# SSD1306.net
KiCad netlist of a schematic drawn in Altium Designer
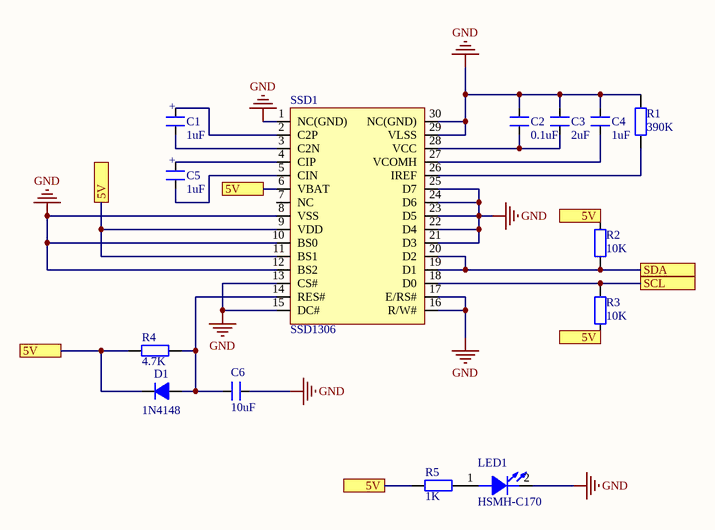
[diagram p0: SSD1306.SchDoc]

(export (version "E")
  (design (tool "Eeschema 10.0.6"))
  (components
    (comp (ref "C1")
      (value "1uF")
      (footprint "SM-0805")
      (description "Cap SMD")
      (libsource (lib "hphonglib") (part "CM"))
    )
    (comp (ref "C2")
      (value "0.1uF")
      (footprint "SM-0805")
      (description "Cap SMD")
      (libsource (lib "hphonglib") (part "CM"))
    )
    (comp (ref "C3")
      (value "2uF")
      (footprint "SM-0805")
      (description "Cap SMD")
      (libsource (lib "hphonglib") (part "CM"))
    )
    (comp (ref "C4")
      (value "1uF")
      (footprint "SM-0805")
      (description "Cap SMD")
      (libsource (lib "hphonglib") (part "CM"))
    )
    (comp (ref "C5")
      (value "1uF")
      (footprint "SM-0805")
      (description "Cap SMD")
      (libsource (lib "hphonglib") (part "CM"))
    )
    (comp (ref "C6")
      (value "10uF")
      (footprint "SM-0805")
      (description "Cap SMD")
      (libsource (lib "hphonglib") (part "CM"))
    )
    (comp (ref "D1")
      (value "Diode")
      (footprint "DO-214AC,SMA")
      (fields (field (name "PUBLISHER") "Altium Limited"))
      (libsource (lib "hphonglib") (part "Diode"))
    )
    (comp (ref "LED1")
      (value "HSMH-C170")
      (footprint "LED.SMD.GREEN")
      (description "Typical GaAs SMD LED")
      (fields (field (name "MANUFACTURER") "Lite-On Inc") (field (name "PUBLISHER") "Hoang Nguyen"))
      (libsource (lib "hphonglib") (part "LED_1"))
    )
    (comp (ref "R1")
      (value "390K")
      (footprint "DIEN TRO 0805")
      (description "RES_0805")
      (fields (field (name "Comment") "RES_SMD_0805") (field (name "PUBLISHER") "Altium Limited"))
      (libsource (lib "") (part "RES_SMD_0805_1"))
    )
    (comp (ref "R2")
      (value "10K")
      (footprint "DIEN TRO 0805")
      (description "RES_0805")
      (fields (field (name "Comment") "RES_SMD_0805") (field (name "PUBLISHER") "Altium Limited"))
      (libsource (lib "") (part "RES_SMD_0805_1"))
    )
    (comp (ref "R3")
      (value "10K")
      (footprint "DIEN TRO 0805")
      (description "RES_0805")
      (fields (field (name "Comment") "RES_SMD_0805") (field (name "PUBLISHER") "Altium Limited"))
      (libsource (lib "") (part "RES_SMD_0805_1"))
    )
    (comp (ref "R4")
      (value "4.7K")
      (footprint "DIEN TRO 0805")
      (description "RES_0805")
      (fields (field (name "Comment") "RES_SMD_0805") (field (name "PUBLISHER") "Altium Limited"))
      (libsource (lib "hphonglib") (part "RES_SMD_0805"))
    )
    (comp (ref "R5")
      (value "1K")
      (footprint "DIEN TRO 0805")
      (description "RES_0805")
      (fields (field (name "Comment") "RES_SMD_0805") (field (name "PUBLISHER") "Altium Limited"))
      (libsource (lib "hphonglib") (part "RES_SMD_0805"))
    )
    (comp (ref "SSD1")
      (value "SSD1306")
      (footprint "SSD1306")
      (libsource (lib "EMG_IoT_V2.0") (part "SSD1306"))
    )
  )
  (nets
    (net (code "1") (name "/5V") (class "Default")
      (node (ref "D1") (pin "2") (pinfunction "K_2") (pintype "passive"))
      (node (ref "R2") (pin "2") (pinfunction "2_2") (pintype "passive"))
      (node (ref "R3") (pin "1") (pinfunction "1_1") (pintype "passive"))
      (node (ref "R4") (pin "1") (pinfunction "1_1") (pintype "passive"))
      (node (ref "R5") (pin "1") (pinfunction "1_1") (pintype "passive"))
      (node (ref "SSD1") (pin "11") (pinfunction "BS1_11") (pintype "passive"))
      (node (ref "SSD1") (pin "6") (pinfunction "VBAT_6") (pintype "passive"))
      (node (ref "SSD1") (pin "9") (pinfunction "VDD_9") (pintype "passive"))
    )
    (net (code "2") (name "/SCL") (class "Default")
      (node (ref "R3") (pin "2") (pinfunction "2_2") (pintype "passive"))
      (node (ref "SSD1") (pin "18") (pinfunction "D0_18") (pintype "passive"))
    )
    (net (code "3") (name "/SDA") (class "Default")
      (node (ref "R2") (pin "1") (pinfunction "1_1") (pintype "passive"))
      (node (ref "SSD1") (pin "19") (pinfunction "D1_19") (pintype "passive"))
      (node (ref "SSD1") (pin "20") (pinfunction "D2_20") (pintype "passive"))
    )
    (net (code "4") (name "GND") (class "Default")
      (node (ref "C2") (pin "2") (pinfunction "2_2") (pintype "passive"))
      (node (ref "C3") (pin "2") (pinfunction "2_2") (pintype "passive"))
      (node (ref "C4") (pin "2") (pinfunction "2_2") (pintype "passive"))
      (node (ref "C6") (pin "2") (pinfunction "2_2") (pintype "passive"))
      (node (ref "LED1") (pin "2") (pinfunction "K_2") (pintype "passive"))
      (node (ref "R1") (pin "2") (pinfunction "2_2") (pintype "passive"))
      (node (ref "SSD1") (pin "1") (pinfunction "NC(GND)_1") (pintype "passive"))
      (node (ref "SSD1") (pin "10") (pinfunction "BS0_10") (pintype "passive"))
      (node (ref "SSD1") (pin "12") (pinfunction "BS2_12") (pintype "passive"))
      (node (ref "SSD1") (pin "13") (pinfunction "CS#_13") (pintype "passive"))
      (node (ref "SSD1") (pin "15") (pinfunction "DC#_15") (pintype "passive"))
      (node (ref "SSD1") (pin "16") (pinfunction "R/W#_16") (pintype "passive"))
      (node (ref "SSD1") (pin "17") (pinfunction "E/RS#_17") (pintype "passive"))
      (node (ref "SSD1") (pin "21") (pinfunction "D3_21") (pintype "passive"))
      (node (ref "SSD1") (pin "22") (pinfunction "D4_22") (pintype "passive"))
      (node (ref "SSD1") (pin "23") (pinfunction "D5_23") (pintype "passive"))
      (node (ref "SSD1") (pin "24") (pinfunction "D6_24") (pintype "passive"))
      (node (ref "SSD1") (pin "25") (pinfunction "D7_25") (pintype "passive"))
      (node (ref "SSD1") (pin "29") (pinfunction "VLSS_29") (pintype "passive"))
      (node (ref "SSD1") (pin "30") (pinfunction "NC(GND)_30") (pintype "passive"))
      (node (ref "SSD1") (pin "8") (pinfunction "VSS_8") (pintype "passive"))
    )
    (net (code "5") (name "Net-(D1-A)") (class "Default")
      (node (ref "C6") (pin "1") (pinfunction "1_1") (pintype "passive"))
      (node (ref "D1") (pin "1") (pinfunction "A_1") (pintype "passive"))
      (node (ref "R4") (pin "2") (pinfunction "2_2") (pintype "passive"))
      (node (ref "SSD1") (pin "14") (pinfunction "RES#_14") (pintype "passive"))
    )
    (net (code "6") (name "Net-(LED1-A)") (class "Default")
      (node (ref "LED1") (pin "1") (pinfunction "A_1") (pintype "passive"))
      (node (ref "R5") (pin "2") (pinfunction "2_2") (pintype "passive"))
    )
    (net (code "7") (name "Net-(SSD1-C2N)") (class "Default")
      (node (ref "C1") (pin "1") (pinfunction "1_1") (pintype "passive"))
      (node (ref "SSD1") (pin "3") (pinfunction "C2N_3") (pintype "passive"))
    )
    (net (code "8") (name "Net-(SSD1-C2P)") (class "Default")
      (node (ref "C1") (pin "2") (pinfunction "2_2") (pintype "passive"))
      (node (ref "SSD1") (pin "2") (pinfunction "C2P_2") (pintype "passive"))
    )
    (net (code "9") (name "Net-(SSD1-CIN)") (class "Default")
      (node (ref "C5") (pin "1") (pinfunction "1_1") (pintype "passive"))
      (node (ref "SSD1") (pin "5") (pinfunction "CIN_5") (pintype "passive"))
    )
    (net (code "10") (name "Net-(SSD1-CIP)") (class "Default")
      (node (ref "C5") (pin "2") (pinfunction "2_2") (pintype "passive"))
      (node (ref "SSD1") (pin "4") (pinfunction "CIP_4") (pintype "passive"))
    )
    (net (code "11") (name "Net-(SSD1-IREF)") (class "Default")
      (node (ref "R1") (pin "1") (pinfunction "1_1") (pintype "passive"))
      (node (ref "SSD1") (pin "26") (pinfunction "IREF_26") (pintype "passive"))
    )
    (net (code "12") (name "Net-(SSD1-VCC)") (class "Default")
      (node (ref "C2") (pin "1") (pinfunction "1_1") (pintype "passive"))
      (node (ref "C3") (pin "1") (pinfunction "1_1") (pintype "passive"))
      (node (ref "SSD1") (pin "28") (pinfunction "VCC_28") (pintype "passive"))
    )
    (net (code "13") (name "Net-(SSD1-VCOMH)") (class "Default")
      (node (ref "C4") (pin "1") (pinfunction "1_1") (pintype "passive"))
      (node (ref "SSD1") (pin "27") (pinfunction "VCOMH_27") (pintype "passive"))
    )
    (net (code "14") (name "unconnected-(SSD1-NC-Pad7)") (class "Default")
      (node (ref "SSD1") (pin "7") (pinfunction "NC_7") (pintype "passive"))
    )
  )
)
